# PCB-TBAR-BO.net
KiCad netlist of a schematic drawn in EAGLE
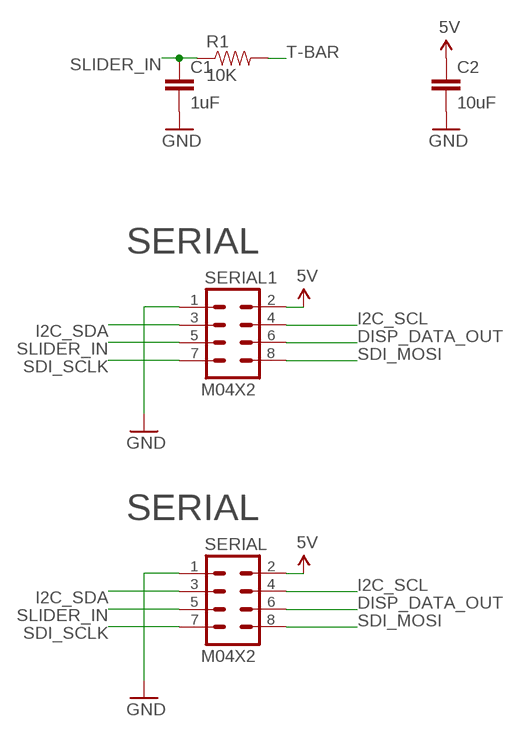
[diagram p0: schematic, sheet 1]

(export (version "E")
  (design (tool "Eeschema 10.0.6"))
  (components
    (comp (ref "C1")
      (value "1uF")
      (footprint "eagle-import:0603-CAP")
      (libsource (lib "eagle-import") (part "CAP0603-CAP"))
    )
    (comp (ref "C2")
      (value "10uF")
      (footprint "eagle-import:0603-CAP")
      (libsource (lib "eagle-import") (part "CAP0603-CAP"))
    )
    (comp (ref "R1")
      (value "10K")
      (footprint "eagle-import:0603-RES")
      (libsource (lib "eagle-import") (part "RESISTOR0603-RES"))
    )
    (comp (ref "SERIAL")
      (value "M04X2")
      (footprint "eagle-import:2X4")
      (libsource (lib "eagle-import") (part "M04X2"))
    )
    (comp (ref "SERIAL1")
      (value "M04X2")
      (footprint "eagle-import:2X4")
      (libsource (lib "eagle-import") (part "M04X2"))
    )
  )
  (nets
    (net (code "1") (name "/DISP_DATA_OUT") (class "Default")
      (node (ref "SERIAL") (pin "6") (pinfunction "6_6") (pintype "passive"))
      (node (ref "SERIAL1") (pin "6") (pinfunction "6_6") (pintype "passive"))
    )
    (net (code "2") (name "/I2C_SCL") (class "Default")
      (node (ref "SERIAL") (pin "4") (pinfunction "4_4") (pintype "passive"))
      (node (ref "SERIAL1") (pin "4") (pinfunction "4_4") (pintype "passive"))
    )
    (net (code "3") (name "/I2C_SDA") (class "Default")
      (node (ref "SERIAL") (pin "3") (pinfunction "3_3") (pintype "passive"))
      (node (ref "SERIAL1") (pin "3") (pinfunction "3_3") (pintype "passive"))
    )
    (net (code "4") (name "/SDI_MOSI") (class "Default")
      (node (ref "SERIAL") (pin "8") (pinfunction "8_8") (pintype "passive"))
      (node (ref "SERIAL1") (pin "8") (pinfunction "8_8") (pintype "passive"))
    )
    (net (code "5") (name "/SDI_SCLK") (class "Default")
      (node (ref "SERIAL") (pin "7") (pinfunction "7_7") (pintype "passive"))
      (node (ref "SERIAL1") (pin "7") (pinfunction "7_7") (pintype "passive"))
    )
    (net (code "6") (name "/SLIDER_IN") (class "Default")
      (node (ref "C1") (pin "1") (pinfunction "1_1") (pintype "passive"))
      (node (ref "R1") (pin "1") (pinfunction "1_1") (pintype "passive"))
      (node (ref "SERIAL") (pin "5") (pinfunction "5_5") (pintype "passive"))
      (node (ref "SERIAL1") (pin "5") (pinfunction "5_5") (pintype "passive"))
    )
    (net (code "7") (name "/T-BAR") (class "Default")
      (node (ref "R1") (pin "2") (pinfunction "2_2") (pintype "passive"))
    )
    (net (code "8") (name "5V") (class "Default")
      (node (ref "C2") (pin "1") (pinfunction "1_1") (pintype "passive"))
      (node (ref "SERIAL") (pin "2") (pinfunction "2_2") (pintype "passive"))
      (node (ref "SERIAL1") (pin "2") (pinfunction "2_2") (pintype "passive"))
    )
    (net (code "9") (name "GND") (class "Default")
      (node (ref "C1") (pin "2") (pinfunction "2_2") (pintype "passive"))
      (node (ref "C2") (pin "2") (pinfunction "2_2") (pintype "passive"))
      (node (ref "SERIAL") (pin "1") (pinfunction "1_1") (pintype "passive"))
      (node (ref "SERIAL1") (pin "1") (pinfunction "1_1") (pintype "passive"))
    )
  )
)
